# LscanLVDSdriver.net
KiCad netlist of a schematic drawn in Altium Designer
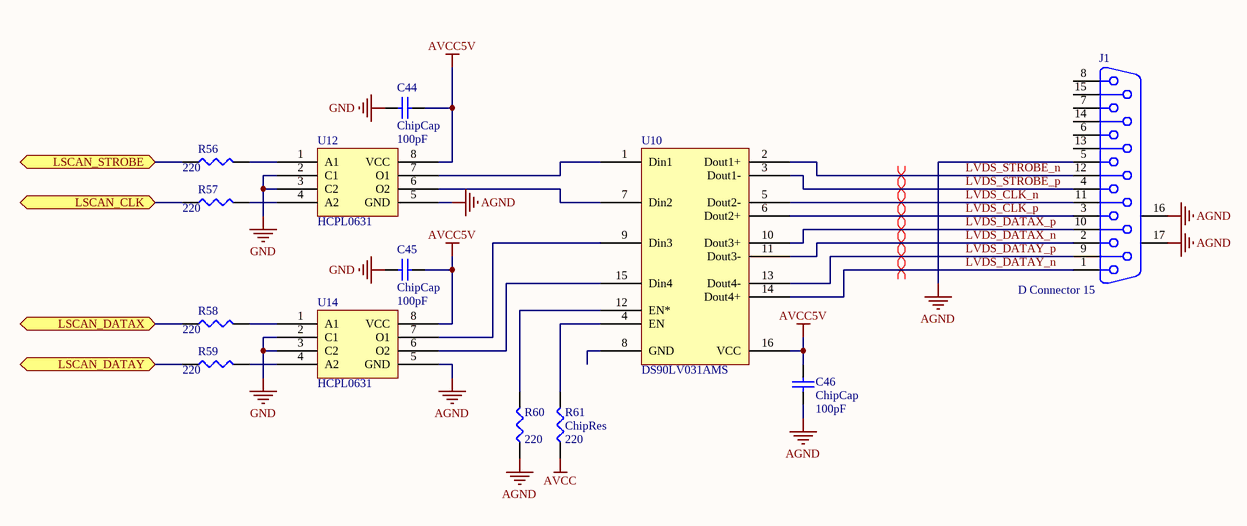
[diagram p0: LscanLVDSdriver.SchDoc]

(export (version "E")
  (design (tool "Eeschema 10.0.6"))
  (components
    (comp (ref "C44")
      (value "ChipCap")
      (footprint "CAP0805")
      (description "Capacitor")
      (fields (field (name "ALTIUM_VALUE") "100pF") (field (name "PUBLISHER") "Altium Limited"))
      (libsource (lib "Common Devices") (part "ChipCap"))
    )
    (comp (ref "C45")
      (value "ChipCap")
      (footprint "CAP0805")
      (description "Capacitor")
      (fields (field (name "ALTIUM_VALUE") "100pF") (field (name "PUBLISHER") "Altium Limited"))
      (libsource (lib "Common Devices") (part "ChipCap"))
    )
    (comp (ref "C46")
      (value "ChipCap")
      (footprint "CAP0805")
      (description "Capacitor")
      (fields (field (name "ALTIUM_VALUE") "100pF") (field (name "PUBLISHER") "Altium Limited"))
      (libsource (lib "Common Devices") (part "ChipCap"))
    )
    (comp (ref "J1")
      (value "D Connector 15")
      (footprint "DSUB1.385-2H15")
      (description "Receptacle Assembly, 15 Position, Right Angle")
      (fields (field (name "PUBLISHER") "Altium Limited"))
      (libsource (lib "Miscellaneous Connectors") (part "D Connector 15"))
    )
    (comp (ref "R56")
      (value "220")
      (footprint "RES0805")
      (description "Chip resistor")
      (fields (field (name "Comment") "ChipRes"))
      (libsource (lib "Common Devices") (part "ChipRes"))
    )
    (comp (ref "R57")
      (value "220")
      (footprint "RES0805")
      (description "Chip resistor")
      (fields (field (name "Comment") "ChipRes"))
      (libsource (lib "Common Devices") (part "ChipRes"))
    )
    (comp (ref "R58")
      (value "220")
      (footprint "RES0805")
      (description "Chip resistor")
      (fields (field (name "Comment") "ChipRes"))
      (libsource (lib "Common Devices") (part "ChipRes"))
    )
    (comp (ref "R59")
      (value "220")
      (footprint "RES0805")
      (description "Chip resistor")
      (fields (field (name "Comment") "ChipRes"))
      (libsource (lib "Common Devices") (part "ChipRes"))
    )
    (comp (ref "R60")
      (value "220")
      (footprint "RES0805")
      (description "Chip resistor")
      (fields (field (name "Comment") "ChipRes"))
      (libsource (lib "Common Devices") (part "ChipRes"))
    )
    (comp (ref "R61")
      (value "ChipRes")
      (footprint "RES0805")
      (description "Chip resistor")
      (fields (field (name "ALTIUM_VALUE") "220"))
      (libsource (lib "Common Devices") (part "ChipRes"))
    )
    (comp (ref "U10")
      (value "DS90LV031AMS")
      (footprint "SOIC16")
      (description "3V LVDS Quad CMOS Differential Line Driver")
      (libsource (lib "TI Step Motor Driver") (part "DS90LV031AMS"))
    )
    (comp (ref "U12")
      (value "HCPL0631")
      (footprint "SOIC8")
      (description "2-channel opto-coupler")
      (libsource (lib "Avago Optocouplers") (part "HCPL0631"))
    )
    (comp (ref "U14")
      (value "HCPL0631")
      (footprint "SOIC8")
      (description "2-channel opto-coupler")
      (libsource (lib "Avago Optocouplers") (part "HCPL0631"))
    )
  )
  (nets
    (net (code "1") (name "/LSCAN_CLK") (class "Default") (node (ref "R57") (pin "1") (pintype "passive")))
    (net (code "2") (name "/LSCAN_DATAX") (class "Default") (node (ref "R58") (pin "1") (pintype "passive")))
    (net (code "3") (name "/LSCAN_DATAY") (class "Default") (node (ref "R59") (pin "1") (pintype "passive")))
    (net (code "4") (name "/LSCAN_STROBE") (class "Default") (node (ref "R56") (pin "1") (pintype "passive")))
    (net (code "5") (name "/LVDS_CLK_n") (class "Default")
      (node (ref "J1") (pin "11") (pinfunction "11_11") (pintype "passive"))
      (node (ref "U10") (pin "5") (pinfunction "Dout2-_5") (pintype "passive"))
    )
    (net (code "6") (name "/LVDS_CLK_p") (class "Default")
      (node (ref "J1") (pin "3") (pinfunction "3_3") (pintype "passive"))
      (node (ref "U10") (pin "6") (pinfunction "Dout2+_6") (pintype "passive"))
    )
    (net (code "7") (name "/LVDS_DATAX_n") (class "Default")
      (node (ref "J1") (pin "2") (pinfunction "2_2") (pintype "passive"))
      (node (ref "U10") (pin "11") (pinfunction "Dout3-_11") (pintype "passive"))
    )
    (net (code "8") (name "/LVDS_DATAX_p") (class "Default")
      (node (ref "J1") (pin "10") (pinfunction "10_10") (pintype "passive"))
      (node (ref "U10") (pin "10") (pinfunction "Dout3+_10") (pintype "passive"))
    )
    (net (code "9") (name "/LVDS_DATAY_n") (class "Default")
      (node (ref "J1") (pin "1") (pinfunction "1_1") (pintype "passive"))
      (node (ref "U10") (pin "14") (pinfunction "Dout4+_14") (pintype "passive"))
    )
    (net (code "10") (name "/LVDS_DATAY_p") (class "Default")
      (node (ref "J1") (pin "9") (pinfunction "9_9") (pintype "passive"))
      (node (ref "U10") (pin "13") (pinfunction "Dout4-_13") (pintype "passive"))
    )
    (net (code "11") (name "/LVDS_STROBE_n") (class "Default")
      (node (ref "J1") (pin "12") (pinfunction "12_12") (pintype "passive"))
      (node (ref "U10") (pin "2") (pinfunction "Dout1+_2") (pintype "passive"))
    )
    (net (code "12") (name "/LVDS_STROBE_p") (class "Default")
      (node (ref "J1") (pin "4") (pinfunction "4_4") (pintype "passive"))
      (node (ref "U10") (pin "3") (pinfunction "Dout1-_3") (pintype "passive"))
    )
    (net (code "13") (name "AGND") (class "Default")
      (node (ref "C46") (pin "1") (pinfunction "1_1") (pintype "passive"))
      (node (ref "J1") (pin "16") (pinfunction "MH1_16") (pintype "passive"))
      (node (ref "J1") (pin "17") (pinfunction "MH2_17") (pintype "passive"))
      (node (ref "J1") (pin "5") (pinfunction "5_5") (pintype "passive"))
      (node (ref "R60") (pin "1") (pintype "passive"))
      (node (ref "U12") (pin "5") (pinfunction "GND_5") (pintype "passive"))
      (node (ref "U14") (pin "5") (pinfunction "GND_5") (pintype "passive"))
    )
    (net (code "14") (name "AVCC") (class "Default") (node (ref "R61") (pin "1") (pintype "passive")))
    (net (code "15") (name "AVCC5V") (class "Default")
      (node (ref "C44") (pin "1") (pinfunction "1_1") (pintype "passive"))
      (node (ref "C45") (pin "1") (pinfunction "1_1") (pintype "passive"))
      (node (ref "C46") (pin "2") (pinfunction "2_2") (pintype "passive"))
      (node (ref "U10") (pin "16") (pinfunction "VCC_16") (pintype "passive"))
      (node (ref "U12") (pin "8") (pinfunction "VCC_8") (pintype "passive"))
      (node (ref "U14") (pin "8") (pinfunction "VCC_8") (pintype "passive"))
    )
    (net (code "16") (name "GND") (class "Default")
      (node (ref "C44") (pin "2") (pinfunction "2_2") (pintype "passive"))
      (node (ref "C45") (pin "2") (pinfunction "2_2") (pintype "passive"))
      (node (ref "U12") (pin "2") (pinfunction "C1_2") (pintype "passive"))
      (node (ref "U12") (pin "3") (pinfunction "C2_3") (pintype "passive"))
      (node (ref "U14") (pin "2") (pinfunction "C1_2") (pintype "passive"))
      (node (ref "U14") (pin "3") (pinfunction "C2_3") (pintype "passive"))
    )
    (net (code "17") (name "Net-(U10-Din1)") (class "Default")
      (node (ref "U10") (pin "1") (pinfunction "Din1_1") (pintype "passive"))
      (node (ref "U12") (pin "7") (pinfunction "O1_7") (pintype "passive"))
    )
    (net (code "18") (name "Net-(U10-Din2)") (class "Default")
      (node (ref "U10") (pin "7") (pinfunction "Din2_7") (pintype "passive"))
      (node (ref "U12") (pin "6") (pinfunction "O2_6") (pintype "passive"))
    )
    (net (code "19") (name "Net-(U10-Din3)") (class "Default")
      (node (ref "U10") (pin "9") (pinfunction "Din3_9") (pintype "passive"))
      (node (ref "U14") (pin "7") (pinfunction "O1_7") (pintype "passive"))
    )
    (net (code "20") (name "Net-(U10-Din4)") (class "Default")
      (node (ref "U10") (pin "15") (pinfunction "Din4_15") (pintype "passive"))
      (node (ref "U14") (pin "6") (pinfunction "O2_6") (pintype "passive"))
    )
    (net (code "21") (name "Net-(U10-EN)") (class "Default")
      (node (ref "R61") (pin "2") (pintype "passive"))
      (node (ref "U10") (pin "4") (pinfunction "EN_4") (pintype "passive"))
    )
    (net (code "22") (name "Net-(U10-EN*)") (class "Default")
      (node (ref "R60") (pin "2") (pintype "passive"))
      (node (ref "U10") (pin "12") (pinfunction "EN*_12") (pintype "passive"))
    )
    (net (code "23") (name "Net-(U12-A1)") (class "Default")
      (node (ref "R56") (pin "2") (pintype "passive"))
      (node (ref "U12") (pin "1") (pinfunction "A1_1") (pintype "passive"))
    )
    (net (code "24") (name "Net-(U12-A2)") (class "Default")
      (node (ref "R57") (pin "2") (pintype "passive"))
      (node (ref "U12") (pin "4") (pinfunction "A2_4") (pintype "passive"))
    )
    (net (code "25") (name "Net-(U14-A1)") (class "Default")
      (node (ref "R58") (pin "2") (pintype "passive"))
      (node (ref "U14") (pin "1") (pinfunction "A1_1") (pintype "passive"))
    )
    (net (code "26") (name "Net-(U14-A2)") (class "Default")
      (node (ref "R59") (pin "2") (pintype "passive"))
      (node (ref "U14") (pin "4") (pinfunction "A2_4") (pintype "passive"))
    )
    (net (code "27") (name "unconnected-(J1-Pad6)") (class "Default")
      (node (ref "J1") (pin "6") (pinfunction "6_6") (pintype "passive"))
    )
    (net (code "28") (name "unconnected-(J1-Pad7)") (class "Default")
      (node (ref "J1") (pin "7") (pinfunction "7_7") (pintype "passive"))
    )
    (net (code "29") (name "unconnected-(J1-Pad8)") (class "Default")
      (node (ref "J1") (pin "8") (pinfunction "8_8") (pintype "passive"))
    )
    (net (code "30") (name "unconnected-(J1-Pad13)") (class "Default")
      (node (ref "J1") (pin "13") (pinfunction "13_13") (pintype "passive"))
    )
    (net (code "31") (name "unconnected-(J1-Pad14)") (class "Default")
      (node (ref "J1") (pin "14") (pinfunction "14_14") (pintype "passive"))
    )
    (net (code "32") (name "unconnected-(J1-Pad15)") (class "Default")
      (node (ref "J1") (pin "15") (pinfunction "15_15") (pintype "passive"))
    )
    (net (code "33") (name "unconnected-(U10-GND-Pad8)") (class "Default")
      (node (ref "U10") (pin "8") (pinfunction "GND_8") (pintype "passive"))
    )
  )
)
